# main.net
KiCad netlist of a schematic drawn in EAGLE
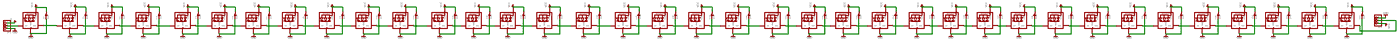
[diagram p0: schematic, sheet 1, overview]
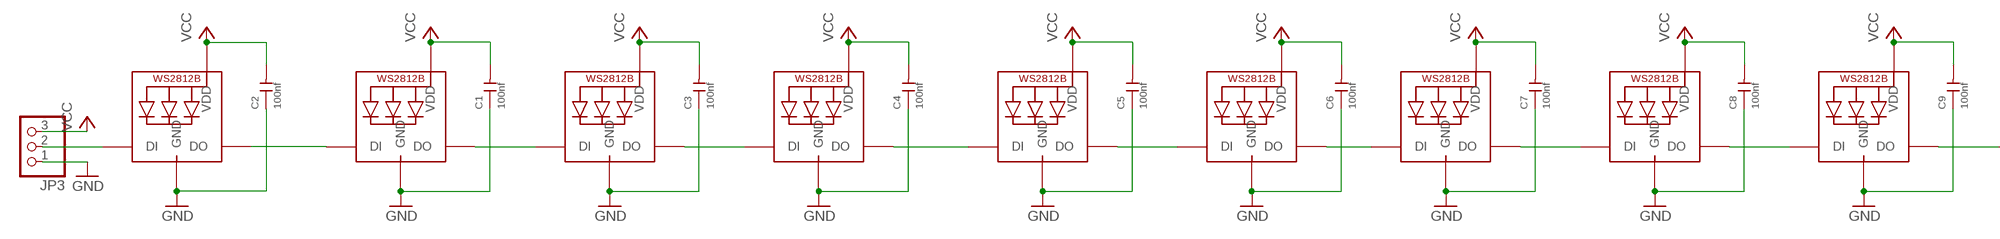
[diagram p1: schematic, sheet 1, part 1 of 4]
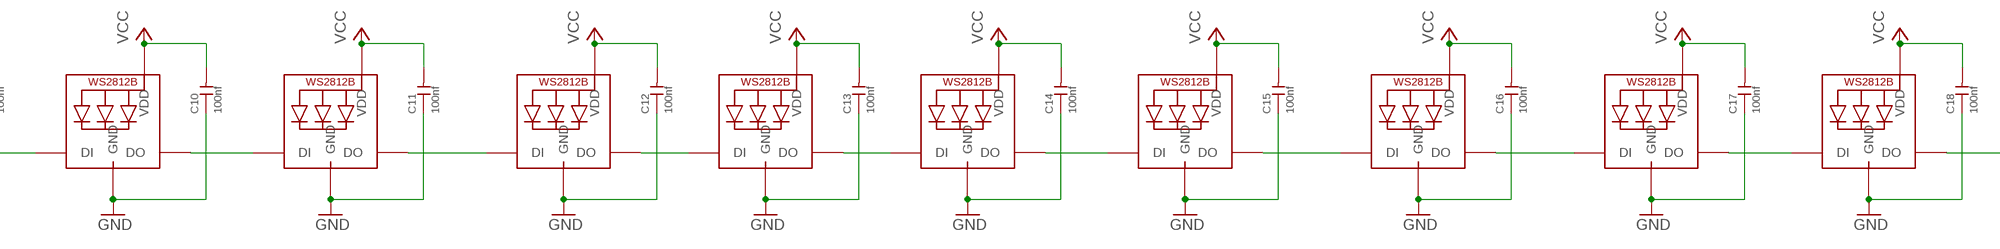
[diagram p2: schematic, sheet 1, part 2 of 4]
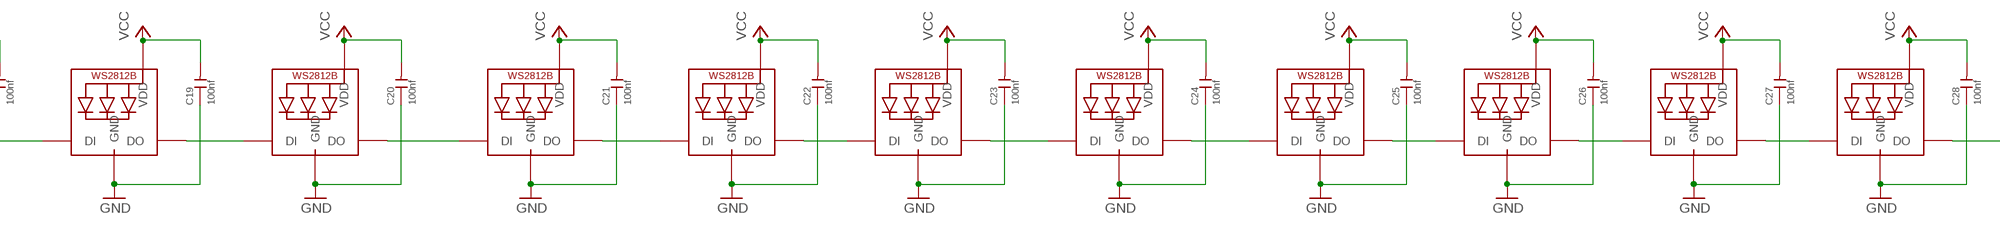
[diagram p3: schematic, sheet 1, part 3 of 4]
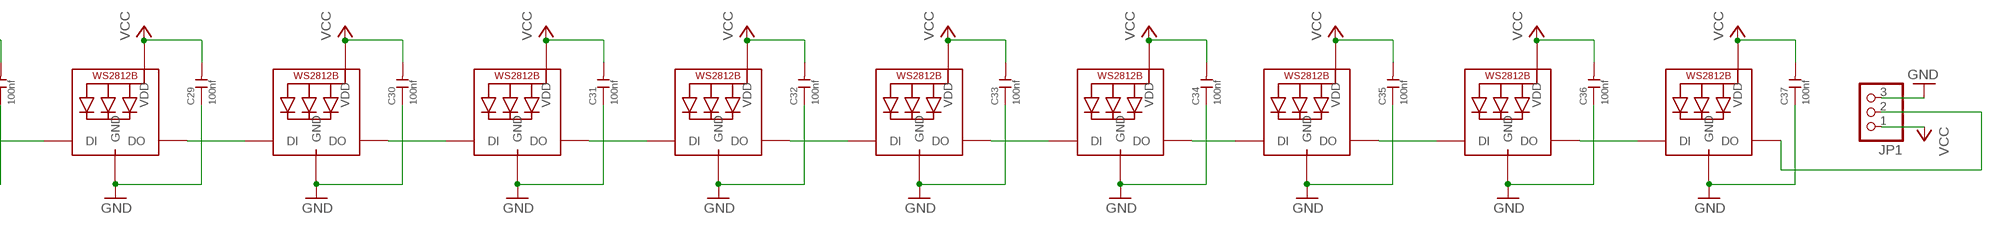
[diagram p4: schematic, sheet 1, part 4 of 4]

(export (version "E")
  (design (tool "Eeschema 10.0.6"))
  (components
    (comp (ref "C1")
      (value "100nf")
      (footprint "eagle-import:C0805")
      (fields (field (name "MPN") "CC0805KRX7R9BB104"))
      (libsource (lib "eagle-import") (part "CERAMIC-100NF-50V-10%-X7R(0805)"))
    )
    (comp (ref "C2")
      (value "100nf")
      (footprint "eagle-import:C0805")
      (fields (field (name "MPN") "CC0805KRX7R9BB104"))
      (libsource (lib "eagle-import") (part "CERAMIC-100NF-50V-10%-X7R(0805)"))
    )
    (comp (ref "C3")
      (value "100nf")
      (footprint "eagle-import:C0805")
      (fields (field (name "MPN") "CC0805KRX7R9BB104"))
      (libsource (lib "eagle-import") (part "CERAMIC-100NF-50V-10%-X7R(0805)"))
    )
    (comp (ref "C4")
      (value "100nf")
      (footprint "eagle-import:C0805")
      (fields (field (name "MPN") "CC0805KRX7R9BB104"))
      (libsource (lib "eagle-import") (part "CERAMIC-100NF-50V-10%-X7R(0805)"))
    )
    (comp (ref "C5")
      (value "100nf")
      (footprint "eagle-import:C0805")
      (fields (field (name "MPN") "CC0805KRX7R9BB104"))
      (libsource (lib "eagle-import") (part "CERAMIC-100NF-50V-10%-X7R(0805)"))
    )
    (comp (ref "C6")
      (value "100nf")
      (footprint "eagle-import:C0805")
      (fields (field (name "MPN") "CC0805KRX7R9BB104"))
      (libsource (lib "eagle-import") (part "CERAMIC-100NF-50V-10%-X7R(0805)"))
    )
    (comp (ref "C7")
      (value "100nf")
      (footprint "eagle-import:C0805")
      (fields (field (name "MPN") "CC0805KRX7R9BB104"))
      (libsource (lib "eagle-import") (part "CERAMIC-100NF-50V-10%-X7R(0805)"))
    )
    (comp (ref "C8")
      (value "100nf")
      (footprint "eagle-import:C0805")
      (fields (field (name "MPN") "CC0805KRX7R9BB104"))
      (libsource (lib "eagle-import") (part "CERAMIC-100NF-50V-10%-X7R(0805)"))
    )
    (comp (ref "C9")
      (value "100nf")
      (footprint "eagle-import:C0805")
      (fields (field (name "MPN") "CC0805KRX7R9BB104"))
      (libsource (lib "eagle-import") (part "CERAMIC-100NF-50V-10%-X7R(0805)"))
    )
    (comp (ref "C10")
      (value "100nf")
      (footprint "eagle-import:C0805")
      (fields (field (name "MPN") "CC0805KRX7R9BB104"))
      (libsource (lib "eagle-import") (part "CERAMIC-100NF-50V-10%-X7R(0805)"))
    )
    (comp (ref "C11")
      (value "100nf")
      (footprint "eagle-import:C0805")
      (fields (field (name "MPN") "CC0805KRX7R9BB104"))
      (libsource (lib "eagle-import") (part "CERAMIC-100NF-50V-10%-X7R(0805)"))
    )
    (comp (ref "C12")
      (value "100nf")
      (footprint "eagle-import:C0805")
      (fields (field (name "MPN") "CC0805KRX7R9BB104"))
      (libsource (lib "eagle-import") (part "CERAMIC-100NF-50V-10%-X7R(0805)"))
    )
    (comp (ref "C13")
      (value "100nf")
      (footprint "eagle-import:C0805")
      (fields (field (name "MPN") "CC0805KRX7R9BB104"))
      (libsource (lib "eagle-import") (part "CERAMIC-100NF-50V-10%-X7R(0805)"))
    )
    (comp (ref "C14")
      (value "100nf")
      (footprint "eagle-import:C0805")
      (fields (field (name "MPN") "CC0805KRX7R9BB104"))
      (libsource (lib "eagle-import") (part "CERAMIC-100NF-50V-10%-X7R(0805)"))
    )
    (comp (ref "C15")
      (value "100nf")
      (footprint "eagle-import:C0805")
      (fields (field (name "MPN") "CC0805KRX7R9BB104"))
      (libsource (lib "eagle-import") (part "CERAMIC-100NF-50V-10%-X7R(0805)"))
    )
    (comp (ref "C16")
      (value "100nf")
      (footprint "eagle-import:C0805")
      (fields (field (name "MPN") "CC0805KRX7R9BB104"))
      (libsource (lib "eagle-import") (part "CERAMIC-100NF-50V-10%-X7R(0805)"))
    )
    (comp (ref "C17")
      (value "100nf")
      (footprint "eagle-import:C0805")
      (fields (field (name "MPN") "CC0805KRX7R9BB104"))
      (libsource (lib "eagle-import") (part "CERAMIC-100NF-50V-10%-X7R(0805)"))
    )
    (comp (ref "C18")
      (value "100nf")
      (footprint "eagle-import:C0805")
      (fields (field (name "MPN") "CC0805KRX7R9BB104"))
      (libsource (lib "eagle-import") (part "CERAMIC-100NF-50V-10%-X7R(0805)"))
    )
    (comp (ref "C19")
      (value "100nf")
      (footprint "eagle-import:C0805")
      (fields (field (name "MPN") "CC0805KRX7R9BB104"))
      (libsource (lib "eagle-import") (part "CERAMIC-100NF-50V-10%-X7R(0805)"))
    )
    (comp (ref "C20")
      (value "100nf")
      (footprint "eagle-import:C0805")
      (fields (field (name "MPN") "CC0805KRX7R9BB104"))
      (libsource (lib "eagle-import") (part "CERAMIC-100NF-50V-10%-X7R(0805)"))
    )
    (comp (ref "C21")
      (value "100nf")
      (footprint "eagle-import:C0805")
      (fields (field (name "MPN") "CC0805KRX7R9BB104"))
      (libsource (lib "eagle-import") (part "CERAMIC-100NF-50V-10%-X7R(0805)"))
    )
    (comp (ref "C22")
      (value "100nf")
      (footprint "eagle-import:C0805")
      (fields (field (name "MPN") "CC0805KRX7R9BB104"))
      (libsource (lib "eagle-import") (part "CERAMIC-100NF-50V-10%-X7R(0805)"))
    )
    (comp (ref "C23")
      (value "100nf")
      (footprint "eagle-import:C0805")
      (fields (field (name "MPN") "CC0805KRX7R9BB104"))
      (libsource (lib "eagle-import") (part "CERAMIC-100NF-50V-10%-X7R(0805)"))
    )
    (comp (ref "C24")
      (value "100nf")
      (footprint "eagle-import:C0805")
      (fields (field (name "MPN") "CC0805KRX7R9BB104"))
      (libsource (lib "eagle-import") (part "CERAMIC-100NF-50V-10%-X7R(0805)"))
    )
    (comp (ref "C25")
      (value "100nf")
      (footprint "eagle-import:C0805")
      (fields (field (name "MPN") "CC0805KRX7R9BB104"))
      (libsource (lib "eagle-import") (part "CERAMIC-100NF-50V-10%-X7R(0805)"))
    )
    (comp (ref "C26")
      (value "100nf")
      (footprint "eagle-import:C0805")
      (fields (field (name "MPN") "CC0805KRX7R9BB104"))
      (libsource (lib "eagle-import") (part "CERAMIC-100NF-50V-10%-X7R(0805)"))
    )
    (comp (ref "C27")
      (value "100nf")
      (footprint "eagle-import:C0805")
      (fields (field (name "MPN") "CC0805KRX7R9BB104"))
      (libsource (lib "eagle-import") (part "CERAMIC-100NF-50V-10%-X7R(0805)"))
    )
    (comp (ref "C28")
      (value "100nf")
      (footprint "eagle-import:C0805")
      (fields (field (name "MPN") "CC0805KRX7R9BB104"))
      (libsource (lib "eagle-import") (part "CERAMIC-100NF-50V-10%-X7R(0805)"))
    )
    (comp (ref "C29")
      (value "100nf")
      (footprint "eagle-import:C0805")
      (fields (field (name "MPN") "CC0805KRX7R9BB104"))
      (libsource (lib "eagle-import") (part "CERAMIC-100NF-50V-10%-X7R(0805)"))
    )
    (comp (ref "C30")
      (value "100nf")
      (footprint "eagle-import:C0805")
      (fields (field (name "MPN") "CC0805KRX7R9BB104"))
      (libsource (lib "eagle-import") (part "CERAMIC-100NF-50V-10%-X7R(0805)"))
    )
    (comp (ref "C31")
      (value "100nf")
      (footprint "eagle-import:C0805")
      (fields (field (name "MPN") "CC0805KRX7R9BB104"))
      (libsource (lib "eagle-import") (part "CERAMIC-100NF-50V-10%-X7R(0805)"))
    )
    (comp (ref "C32")
      (value "100nf")
      (footprint "eagle-import:C0805")
      (fields (field (name "MPN") "CC0805KRX7R9BB104"))
      (libsource (lib "eagle-import") (part "CERAMIC-100NF-50V-10%-X7R(0805)"))
    )
    (comp (ref "C33")
      (value "100nf")
      (footprint "eagle-import:C0805")
      (fields (field (name "MPN") "CC0805KRX7R9BB104"))
      (libsource (lib "eagle-import") (part "CERAMIC-100NF-50V-10%-X7R(0805)"))
    )
    (comp (ref "C34")
      (value "100nf")
      (footprint "eagle-import:C0805")
      (fields (field (name "MPN") "CC0805KRX7R9BB104"))
      (libsource (lib "eagle-import") (part "CERAMIC-100NF-50V-10%-X7R(0805)"))
    )
    (comp (ref "C35")
      (value "100nf")
      (footprint "eagle-import:C0805")
      (fields (field (name "MPN") "CC0805KRX7R9BB104"))
      (libsource (lib "eagle-import") (part "CERAMIC-100NF-50V-10%-X7R(0805)"))
    )
    (comp (ref "C36")
      (value "100nf")
      (footprint "eagle-import:C0805")
      (fields (field (name "MPN") "CC0805KRX7R9BB104"))
      (libsource (lib "eagle-import") (part "CERAMIC-100NF-50V-10%-X7R(0805)"))
    )
    (comp (ref "C37")
      (value "100nf")
      (footprint "eagle-import:C0805")
      (fields (field (name "MPN") "CC0805KRX7R9BB104"))
      (libsource (lib "eagle-import") (part "CERAMIC-100NF-50V-10%-X7R(0805)"))
    )
    (comp (ref "JP1")
      (value "PINHD-1X3")
      (footprint "eagle-import:1X03")
      (libsource (lib "eagle-import") (part "PINHD-1X3"))
    )
    (comp (ref "JP3")
      (value "PINHD-1X3")
      (footprint "eagle-import:1X03")
      (libsource (lib "eagle-import") (part "PINHD-1X3"))
    )
    (comp (ref "L")
      (value "WS2812B5050")
      (footprint "eagle-import:WS2812B")
      (libsource (lib "eagle-import") (part "WS2812B5050"))
    )
    (comp (ref "LED1")
      (value "WS2812B5050")
      (footprint "eagle-import:WS2812B")
      (libsource (lib "eagle-import") (part "WS2812B5050"))
    )
    (comp (ref "LED3")
      (value "WS2812B5050")
      (footprint "eagle-import:WS2812B")
      (libsource (lib "eagle-import") (part "WS2812B5050"))
    )
    (comp (ref "LED4")
      (value "WS2812B5050")
      (footprint "eagle-import:WS2812B")
      (libsource (lib "eagle-import") (part "WS2812B5050"))
    )
    (comp (ref "LED5")
      (value "WS2812B5050")
      (footprint "eagle-import:WS2812B")
      (libsource (lib "eagle-import") (part "WS2812B5050"))
    )
    (comp (ref "LED6")
      (value "WS2812B5050")
      (footprint "eagle-import:WS2812B")
      (libsource (lib "eagle-import") (part "WS2812B5050"))
    )
    (comp (ref "LED7")
      (value "WS2812B5050")
      (footprint "eagle-import:WS2812B")
      (libsource (lib "eagle-import") (part "WS2812B5050"))
    )
    (comp (ref "LED8")
      (value "WS2812B5050")
      (footprint "eagle-import:WS2812B")
      (libsource (lib "eagle-import") (part "WS2812B5050"))
    )
    (comp (ref "LED9")
      (value "WS2812B5050")
      (footprint "eagle-import:WS2812B")
      (libsource (lib "eagle-import") (part "WS2812B5050"))
    )
    (comp (ref "LED10")
      (value "WS2812B5050")
      (footprint "eagle-import:WS2812B")
      (libsource (lib "eagle-import") (part "WS2812B5050"))
    )
    (comp (ref "LED11")
      (value "WS2812B5050")
      (footprint "eagle-import:WS2812B")
      (libsource (lib "eagle-import") (part "WS2812B5050"))
    )
    (comp (ref "LED12")
      (value "WS2812B5050")
      (footprint "eagle-import:WS2812B")
      (libsource (lib "eagle-import") (part "WS2812B5050"))
    )
    (comp (ref "LED13")
      (value "WS2812B5050")
      (footprint "eagle-import:WS2812B")
      (libsource (lib "eagle-import") (part "WS2812B5050"))
    )
    (comp (ref "LED14")
      (value "WS2812B5050")
      (footprint "eagle-import:WS2812B")
      (libsource (lib "eagle-import") (part "WS2812B5050"))
    )
    (comp (ref "LED15")
      (value "WS2812B5050")
      (footprint "eagle-import:WS2812B")
      (libsource (lib "eagle-import") (part "WS2812B5050"))
    )
    (comp (ref "LED16")
      (value "WS2812B5050")
      (footprint "eagle-import:WS2812B")
      (libsource (lib "eagle-import") (part "WS2812B5050"))
    )
    (comp (ref "LED17")
      (value "WS2812B5050")
      (footprint "eagle-import:WS2812B")
      (libsource (lib "eagle-import") (part "WS2812B5050"))
    )
    (comp (ref "LED18")
      (value "WS2812B5050")
      (footprint "eagle-import:WS2812B")
      (libsource (lib "eagle-import") (part "WS2812B5050"))
    )
    (comp (ref "LED19")
      (value "WS2812B5050")
      (footprint "eagle-import:WS2812B")
      (libsource (lib "eagle-import") (part "WS2812B5050"))
    )
    (comp (ref "LED20")
      (value "WS2812B5050")
      (footprint "eagle-import:WS2812B")
      (libsource (lib "eagle-import") (part "WS2812B5050"))
    )
    (comp (ref "LED21")
      (value "WS2812B5050")
      (footprint "eagle-import:WS2812B")
      (libsource (lib "eagle-import") (part "WS2812B5050"))
    )
    (comp (ref "LED22")
      (value "WS2812B5050")
      (footprint "eagle-import:WS2812B")
      (libsource (lib "eagle-import") (part "WS2812B5050"))
    )
    (comp (ref "LED23")
      (value "WS2812B5050")
      (footprint "eagle-import:WS2812B")
      (libsource (lib "eagle-import") (part "WS2812B5050"))
    )
    (comp (ref "LED24")
      (value "WS2812B5050")
      (footprint "eagle-import:WS2812B")
      (libsource (lib "eagle-import") (part "WS2812B5050"))
    )
    (comp (ref "LED25")
      (value "WS2812B5050")
      (footprint "eagle-import:WS2812B")
      (libsource (lib "eagle-import") (part "WS2812B5050"))
    )
    (comp (ref "LED26")
      (value "WS2812B5050")
      (footprint "eagle-import:WS2812B")
      (libsource (lib "eagle-import") (part "WS2812B5050"))
    )
    (comp (ref "LED27")
      (value "WS2812B5050")
      (footprint "eagle-import:WS2812B")
      (libsource (lib "eagle-import") (part "WS2812B5050"))
    )
    (comp (ref "LED28")
      (value "WS2812B5050")
      (footprint "eagle-import:WS2812B")
      (libsource (lib "eagle-import") (part "WS2812B5050"))
    )
    (comp (ref "LED29")
      (value "WS2812B5050")
      (footprint "eagle-import:WS2812B")
      (libsource (lib "eagle-import") (part "WS2812B5050"))
    )
    (comp (ref "LED30")
      (value "WS2812B5050")
      (footprint "eagle-import:WS2812B")
      (libsource (lib "eagle-import") (part "WS2812B5050"))
    )
    (comp (ref "LED31")
      (value "WS2812B5050")
      (footprint "eagle-import:WS2812B")
      (libsource (lib "eagle-import") (part "WS2812B5050"))
    )
    (comp (ref "LED32")
      (value "WS2812B5050")
      (footprint "eagle-import:WS2812B")
      (libsource (lib "eagle-import") (part "WS2812B5050"))
    )
    (comp (ref "LED33")
      (value "WS2812B5050")
      (footprint "eagle-import:WS2812B")
      (libsource (lib "eagle-import") (part "WS2812B5050"))
    )
    (comp (ref "LED34")
      (value "WS2812B5050")
      (footprint "eagle-import:WS2812B")
      (libsource (lib "eagle-import") (part "WS2812B5050"))
    )
    (comp (ref "LED35")
      (value "WS2812B5050")
      (footprint "eagle-import:WS2812B")
      (libsource (lib "eagle-import") (part "WS2812B5050"))
    )
    (comp (ref "LED36")
      (value "WS2812B5050")
      (footprint "eagle-import:WS2812B")
      (libsource (lib "eagle-import") (part "WS2812B5050"))
    )
    (comp (ref "LED37")
      (value "WS2812B5050")
      (footprint "eagle-import:WS2812B")
      (libsource (lib "eagle-import") (part "WS2812B5050"))
    )
  )
  (nets
    (net (code "1") (name "GND") (class "Default")
      (node (ref "C1") (pin "1") (pinfunction "1_1") (pintype "passive"))
      (node (ref "C10") (pin "1") (pinfunction "1_1") (pintype "passive"))
      (node (ref "C11") (pin "1") (pinfunction "1_1") (pintype "passive"))
      (node (ref "C12") (pin "1") (pinfunction "1_1") (pintype "passive"))
      (node (ref "C13") (pin "1") (pinfunction "1_1") (pintype "passive"))
      (node (ref "C14") (pin "1") (pinfunction "1_1") (pintype "passive"))
      (node (ref "C15") (pin "1") (pinfunction "1_1") (pintype "passive"))
      (node (ref "C16") (pin "1") (pinfunction "1_1") (pintype "passive"))
      (node (ref "C17") (pin "1") (pinfunction "1_1") (pintype "passive"))
      (node (ref "C18") (pin "1") (pinfunction "1_1") (pintype "passive"))
      (node (ref "C19") (pin "1") (pinfunction "1_1") (pintype "passive"))
      (node (ref "C2") (pin "1") (pinfunction "1_1") (pintype "passive"))
      (node (ref "C20") (pin "1") (pinfunction "1_1") (pintype "passive"))
      (node (ref "C21") (pin "1") (pinfunction "1_1") (pintype "passive"))
      (node (ref "C22") (pin "1") (pinfunction "1_1") (pintype "passive"))
      (node (ref "C23") (pin "1") (pinfunction "1_1") (pintype "passive"))
      (node (ref "C24") (pin "1") (pinfunction "1_1") (pintype "passive"))
      (node (ref "C25") (pin "1") (pinfunction "1_1") (pintype "passive"))
      (node (ref "C26") (pin "1") (pinfunction "1_1") (pintype "passive"))
      (node (ref "C27") (pin "1") (pinfunction "1_1") (pintype "passive"))
      (node (ref "C28") (pin "1") (pinfunction "1_1") (pintype "passive"))
      (node (ref "C29") (pin "1") (pinfunction "1_1") (pintype "passive"))
      (node (ref "C3") (pin "1") (pinfunction "1_1") (pintype "passive"))
      (node (ref "C30") (pin "1") (pinfunction "1_1") (pintype "passive"))
      (node (ref "C31") (pin "1") (pinfunction "1_1") (pintype "passive"))
      (node (ref "C32") (pin "1") (pinfunction "1_1") (pintype "passive"))
      (node (ref "C33") (pin "1") (pinfunction "1_1") (pintype "passive"))
      (node (ref "C34") (pin "1") (pinfunction "1_1") (pintype "passive"))
      (node (ref "C35") (pin "1") (pinfunction "1_1") (pintype "passive"))
      (node (ref "C36") (pin "1") (pinfunction "1_1") (pintype "passive"))
      (node (ref "C37") (pin "1") (pinfunction "1_1") (pintype "passive"))
      (node (ref "C4") (pin "1") (pinfunction "1_1") (pintype "passive"))
      (node (ref "C5") (pin "1") (pinfunction "1_1") (pintype "passive"))
      (node (ref "C6") (pin "1") (pinfunction "1_1") (pintype "passive"))
      (node (ref "C7") (pin "1") (pinfunction "1_1") (pintype "passive"))
      (node (ref "C8") (pin "1") (pinfunction "1_1") (pintype "passive"))
      (node (ref "C9") (pin "1") (pinfunction "1_1") (pintype "passive"))
      (node (ref "JP1") (pin "3") (pinfunction "3_3") (pintype "passive"))
      (node (ref "JP3") (pin "1") (pinfunction "1_1") (pintype "passive"))
      (node (ref "L") (pin "3-GND") (pinfunction "GND_3-GND") (pintype "power_in"))
      (node (ref "LED1") (pin "3-GND") (pinfunction "GND_3-GND") (pintype "power_in"))
      (node (ref "LED10") (pin "3-GND") (pinfunction "GND_3-GND") (pintype "power_in"))
      (node (ref "LED11") (pin "3-GND") (pinfunction "GND_3-GND") (pintype "power_in"))
      (node (ref "LED12") (pin "3-GND") (pinfunction "GND_3-GND") (pintype "power_in"))
      (node (ref "LED13") (pin "3-GND") (pinfunction "GND_3-GND") (pintype "power_in"))
      (node (ref "LED14") (pin "3-GND") (pinfunction "GND_3-GND") (pintype "power_in"))
      (node (ref "LED15") (pin "3-GND") (pinfunction "GND_3-GND") (pintype "power_in"))
      (node (ref "LED16") (pin "3-GND") (pinfunction "GND_3-GND") (pintype "power_in"))
      (node (ref "LED17") (pin "3-GND") (pinfunction "GND_3-GND") (pintype "power_in"))
      (node (ref "LED18") (pin "3-GND") (pinfunction "GND_3-GND") (pintype "power_in"))
      (node (ref "LED19") (pin "3-GND") (pinfunction "GND_3-GND") (pintype "power_in"))
      (node (ref "LED20") (pin "3-GND") (pinfunction "GND_3-GND") (pintype "power_in"))
      (node (ref "LED21") (pin "3-GND") (pinfunction "GND_3-GND") (pintype "power_in"))
      (node (ref "LED22") (pin "3-GND") (pinfunction "GND_3-GND") (pintype "power_in"))
      (node (ref "LED23") (pin "3-GND") (pinfunction "GND_3-GND") (pintype "power_in"))
      (node (ref "LED24") (pin "3-GND") (pinfunction "GND_3-GND") (pintype "power_in"))
      (node (ref "LED25") (pin "3-GND") (pinfunction "GND_3-GND") (pintype "power_in"))
      (node (ref "LED26") (pin "3-GND") (pinfunction "GND_3-GND") (pintype "power_in"))
      (node (ref "LED27") (pin "3-GND") (pinfunction "GND_3-GND") (pintype "power_in"))
      (node (ref "LED28") (pin "3-GND") (pinfunction "GND_3-GND") (pintype "power_in"))
      (node (ref "LED29") (pin "3-GND") (pinfunction "GND_3-GND") (pintype "power_in"))
      (node (ref "LED3") (pin "3-GND") (pinfunction "GND_3-GND") (pintype "power_in"))
      (node (ref "LED30") (pin "3-GND") (pinfunction "GND_3-GND") (pintype "power_in"))
      (node (ref "LED31") (pin "3-GND") (pinfunction "GND_3-GND") (pintype "power_in"))
      (node (ref "LED32") (pin "3-GND") (pinfunction "GND_3-GND") (pintype "power_in"))
      (node (ref "LED33") (pin "3-GND") (pinfunction "GND_3-GND") (pintype "power_in"))
      (node (ref "LED34") (pin "3-GND") (pinfunction "GND_3-GND") (pintype "power_in"))
      (node (ref "LED35") (pin "3-GND") (pinfunction "GND_3-GND") (pintype "power_in"))
      (node (ref "LED36") (pin "3-GND") (pinfunction "GND_3-GND") (pintype "power_in"))
      (node (ref "LED37") (pin "3-GND") (pinfunction "GND_3-GND") (pintype "power_in"))
      (node (ref "LED4") (pin "3-GND") (pinfunction "GND_3-GND") (pintype "power_in"))
      (node (ref "LED5") (pin "3-GND") (pinfunction "GND_3-GND") (pintype "power_in"))
      (node (ref "LED6") (pin "3-GND") (pinfunction "GND_3-GND") (pintype "power_in"))
      (node (ref "LED7") (pin "3-GND") (pinfunction "GND_3-GND") (pintype "power_in"))
      (node (ref "LED8") (pin "3-GND") (pinfunction "GND_3-GND") (pintype "power_in"))
      (node (ref "LED9") (pin "3-GND") (pinfunction "GND_3-GND") (pintype "power_in"))
    )
    (net (code "2") (name "Net-(L-DI)") (class "Default")
      (node (ref "JP3") (pin "2") (pinfunction "2_2") (pintype "passive"))
      (node (ref "L") (pin "4-DIN") (pinfunction "DI_4-DIN") (pintype "input"))
    )
    (net (code "3") (name "Net-(L-DO)") (class "Default")
      (node (ref "L") (pin "2-DOUT") (pinfunction "DO_2-DOUT") (pintype "output"))
      (node (ref "LED1") (pin "4-DIN") (pinfunction "DI_4-DIN") (pintype "input"))
    )
    (net (code "4") (name "Net-(LED1-DO)") (class "Default")
      (node (ref "LED1") (pin "2-DOUT") (pinfunction "DO_2-DOUT") (pintype "output"))
      (node (ref "LED3") (pin "4-DIN") (pinfunction "DI_4-DIN") (pintype "input"))
    )
    (net (code "5") (name "Net-(LED3-DO)") (class "Default")
      (node (ref "LED3") (pin "2-DOUT") (pinfunction "DO_2-DOUT") (pintype "output"))
      (node (ref "LED4") (pin "4-DIN") (pinfunction "DI_4-DIN") (pintype "input"))
    )
    (net (code "6") (name "Net-(LED4-DO)") (class "Default")
      (node (ref "LED4") (pin "2-DOUT") (pinfunction "DO_2-DOUT") (pintype "output"))
      (node (ref "LED5") (pin "4-DIN") (pinfunction "DI_4-DIN") (pintype "input"))
    )
    (net (code "7") (name "Net-(LED5-DO)") (class "Default")
      (node (ref "LED5") (pin "2-DOUT") (pinfunction "DO_2-DOUT") (pintype "output"))
      (node (ref "LED6") (pin "4-DIN") (pinfunction "DI_4-DIN") (pintype "input"))
    )
    (net (code "8") (name "Net-(LED6-DO)") (class "Default")
      (node (ref "LED6") (pin "2-DOUT") (pinfunction "DO_2-DOUT") (pintype "output"))
      (node (ref "LED7") (pin "4-DIN") (pinfunction "DI_4-DIN") (pintype "input"))
    )
    (net (code "9") (name "Net-(LED7-DO)") (class "Default")
      (node (ref "LED7") (pin "2-DOUT") (pinfunction "DO_2-DOUT") (pintype "output"))
      (node (ref "LED8") (pin "4-DIN") (pinfunction "DI_4-DIN") (pintype "input"))
    )
    (net (code "10") (name "Net-(LED8-DO)") (class "Default")
      (node (ref "LED8") (pin "2-DOUT") (pinfunction "DO_2-DOUT") (pintype "output"))
      (node (ref "LED9") (pin "4-DIN") (pinfunction "DI_4-DIN") (pintype "input"))
    )
    (net (code "11") (name "Net-(LED10-DI)") (class "Default")
      (node (ref "LED10") (pin "4-DIN") (pinfunction "DI_4-DIN") (pintype "input"))
      (node (ref "LED9") (pin "2-DOUT") (pinfunction "DO_2-DOUT") (pintype "output"))
    )
    (net (code "12") (name "Net-(LED10-DO)") (class "Default")
      (node (ref "LED10") (pin "2-DOUT") (pinfunction "DO_2-DOUT") (pintype "output"))
      (node (ref "LED11") (pin "4-DIN") (pinfunction "DI_4-DIN") (pintype "input"))
    )
    (net (code "13") (name "Net-(LED11-DO)") (class "Default")
      (node (ref "LED11") (pin "2-DOUT") (pinfunction "DO_2-DOUT") (pintype "output"))
      (node (ref "LED12") (pin "4-DIN") (pinfunction "DI_4-DIN") (pintype "input"))
    )
    (net (code "14") (name "Net-(LED12-DO)") (class "Default")
      (node (ref "LED12") (pin "2-DOUT") (pinfunction "DO_2-DOUT") (pintype "output"))
      (node (ref "LED13") (pin "4-DIN") (pinfunction "DI_4-DIN") (pintype "input"))
    )
    (net (code "15") (name "Net-(LED13-DO)") (class "Default")
      (node (ref "LED13") (pin "2-DOUT") (pinfunction "DO_2-DOUT") (pintype "output"))
      (node (ref "LED14") (pin "4-DIN") (pinfunction "DI_4-DIN") (pintype "input"))
    )
    (net (code "16") (name "Net-(LED14-DO)") (class "Default")
      (node (ref "LED14") (pin "2-DOUT") (pinfunction "DO_2-DOUT") (pintype "output"))
      (node (ref "LED15") (pin "4-DIN") (pinfunction "DI_4-DIN") (pintype "input"))
    )
    (net (code "17") (name "Net-(LED15-DO)") (class "Default")
      (node (ref "LED15") (pin "2-DOUT") (pinfunction "DO_2-DOUT") (pintype "output"))
      (node (ref "LED16") (pin "4-DIN") (pinfunction "DI_4-DIN") (pintype "input"))
    )
    (net (code "18") (name "Net-(LED16-DO)") (class "Default")
      (node (ref "LED16") (pin "2-DOUT") (pinfunction "DO_2-DOUT") (pintype "output"))
      (node (ref "LED17") (pin "4-DIN") (pinfunction "DI_4-DIN") (pintype "input"))
    )
    (net (code "19") (name "Net-(LED17-DO)") (class "Default")
      (node (ref "LED17") (pin "2-DOUT") (pinfunction "DO_2-DOUT") (pintype "output"))
      (node (ref "LED18") (pin "4-DIN") (pinfunction "DI_4-DIN") (pintype "input"))
    )
    (net (code "20") (name "Net-(LED18-DO)") (class "Default")
      (node (ref "LED18") (pin "2-DOUT") (pinfunction "DO_2-DOUT") (pintype "output"))
      (node (ref "LED19") (pin "4-DIN") (pinfunction "DI_4-DIN") (pintype "input"))
    )
    (net (code "21") (name "Net-(LED19-DO)") (class "Default")
      (node (ref "LED19") (pin "2-DOUT") (pinfunction "DO_2-DOUT") (pintype "output"))
      (node (ref "LED20") (pin "4-DIN") (pinfunction "DI_4-DIN") (pintype "input"))
    )
    (net (code "22") (name "Net-(LED20-DO)") (class "Default")
      (node (ref "LED20") (pin "2-DOUT") (pinfunction "DO_2-DOUT") (pintype "output"))
      (node (ref "LED21") (pin "4-DIN") (pinfunction "DI_4-DIN") (pintype "input"))
    )
    (net (code "23") (name "Net-(LED21-DO)") (class "Default")
      (node (ref "LED21") (pin "2-DOUT") (pinfunction "DO_2-DOUT") (pintype "output"))
      (node (ref "LED22") (pin "4-DIN") (pinfunction "DI_4-DIN") (pintype "input"))
    )
    (net (code "24") (name "Net-(LED22-DO)") (class "Default")
      (node (ref "LED22") (pin "2-DOUT") (pinfunction "DO_2-DOUT") (pintype "output"))
      (node (ref "LED23") (pin "4-DIN") (pinfunction "DI_4-DIN") (pintype "input"))
    )
    (net (code "25") (name "Net-(LED23-DO)") (class "Default")
      (node (ref "LED23") (pin "2-DOUT") (pinfunction "DO_2-DOUT") (pintype "output"))
      (node (ref "LED24") (pin "4-DIN") (pinfunction "DI_4-DIN") (pintype "input"))
    )
    (net (code "26") (name "Net-(LED24-DO)") (class "Default")
      (node (ref "LED24") (pin "2-DOUT") (pinfunction "DO_2-DOUT") (pintype "output"))
      (node (ref "LED25") (pin "4-DIN") (pinfunction "DI_4-DIN") (pintype "input"))
    )
    (net (code "27") (name "Net-(LED25-DO)") (class "Default")
      (node (ref "LED25") (pin "2-DOUT") (pinfunction "DO_2-DOUT") (pintype "output"))
      (node (ref "LED26") (pin "4-DIN") (pinfunction "DI_4-DIN") (pintype "input"))
    )
    (net (code "28") (name "Net-(LED26-DO)") (class "Default")
      (node (ref "LED26") (pin "2-DOUT") (pinfunction "DO_2-DOUT") (pintype "output"))
      (node (ref "LED27") (pin "4-DIN") (pinfunction "DI_4-DIN") (pintype "input"))
    )
    (net (code "29") (name "Net-(LED27-DO)") (class "Default")
      (node (ref "LED27") (pin "2-DOUT") (pinfunction "DO_2-DOUT") (pintype "output"))
      (node (ref "LED28") (pin "4-DIN") (pinfunction "DI_4-DIN") (pintype "input"))
    )
    (net (code "30") (name "Net-(LED28-DO)") (class "Default")
      (node (ref "LED28") (pin "2-DOUT") (pinfunction "DO_2-DOUT") (pintype "output"))
      (node (ref "LED29") (pin "4-DIN") (pinfunction "DI_4-DIN") (pintype "input"))
    )
    (net (code "31") (name "Net-(LED29-DO)") (class "Default")
      (node (ref "LED29") (pin "2-DOUT") (pinfunction "DO_2-DOUT") (pintype "output"))
      (node (ref "LED30") (pin "4-DIN") (pinfunction "DI_4-DIN") (pintype "input"))
    )
    (net (code "32") (name "Net-(LED30-DO)") (class "Default")
      (node (ref "LED30") (pin "2-DOUT") (pinfunction "DO_2-DOUT") (pintype "output"))
      (node (ref "LED31") (pin "4-DIN") (pinfunction "DI_4-DIN") (pintype "input"))
    )
    (net (code "33") (name "Net-(LED31-DO)") (class "Default")
      (node (ref "LED31") (pin "2-DOUT") (pinfunction "DO_2-DOUT") (pintype "output"))
      (node (ref "LED32") (pin "4-DIN") (pinfunction "DI_4-DIN") (pintype "input"))
    )
    (net (code "34") (name "Net-(LED32-DO)") (class "Default")
      (node (ref "LED32") (pin "2-DOUT") (pinfunction "DO_2-DOUT") (pintype "output"))
      (node (ref "LED33") (pin "4-DIN") (pinfunction "DI_4-DIN") (pintype "input"))
    )
    (net (code "35") (name "Net-(LED33-DO)") (class "Default")
      (node (ref "LED33") (pin "2-DOUT") (pinfunction "DO_2-DOUT") (pintype "output"))
      (node (ref "LED34") (pin "4-DIN") (pinfunction "DI_4-DIN") (pintype "input"))
    )
    (net (code "36") (name "Net-(LED34-DO)") (class "Default")
      (node (ref "LED34") (pin "2-DOUT") (pinfunction "DO_2-DOUT") (pintype "output"))
      (node (ref "LED35") (pin "4-DIN") (pinfunction "DI_4-DIN") (pintype "input"))
    )
    (net (code "37") (name "Net-(LED35-DO)") (class "Default")
      (node (ref "LED35") (pin "2-DOUT") (pinfunction "DO_2-DOUT") (pintype "output"))
      (node (ref "LED36") (pin "4-DIN") (pinfunction "DI_4-DIN") (pintype "input"))
    )
    (net (code "38") (name "Net-(LED36-DO)") (class "Default")
      (node (ref "LED36") (pin "2-DOUT") (pinfunction "DO_2-DOUT") (pintype "output"))
      (node (ref "LED37") (pin "4-DIN") (pinfunction "DI_4-DIN") (pintype "input"))
    )
    (net (code "39") (name "Net-(LED37-DO)") (class "Default")
      (node (ref "JP1") (pin "2") (pinfunction "2_2") (pintype "passive"))
      (node (ref "LED37") (pin "2-DOUT") (pinfunction "DO_2-DOUT") (pintype "output"))
    )
    (net (code "40") (name "VCC") (class "Default")
      (node (ref "C1") (pin "2") (pinfunction "2_2") (pintype "passive"))
      (node (ref "C10") (pin "2") (pinfunction "2_2") (pintype "passive"))
      (node (ref "C11") (pin "2") (pinfunction "2_2") (pintype "passive"))
      (node (ref "C12") (pin "2") (pinfunction "2_2") (pintype "passive"))
      (node (ref "C13") (pin "2") (pinfunction "2_2") (pintype "passive"))
      (node (ref "C14") (pin "2") (pinfunction "2_2") (pintype "passive"))
      (node (ref "C15") (pin "2") (pinfunction "2_2") (pintype "passive"))
      (node (ref "C16") (pin "2") (pinfunction "2_2") (pintype "passive"))
      (node (ref "C17") (pin "2") (pinfunction "2_2") (pintype "passive"))
      (node (ref "C18") (pin "2") (pinfunction "2_2") (pintype "passive"))
      (node (ref "C19") (pin "2") (pinfunction "2_2") (pintype "passive"))
      (node (ref "C2") (pin "2") (pinfunction "2_2") (pintype "passive"))
      (node (ref "C20") (pin "2") (pinfunction "2_2") (pintype "passive"))
      (node (ref "C21") (pin "2") (pinfunction "2_2") (pintype "passive"))
      (node (ref "C22") (pin "2") (pinfunction "2_2") (pintype "passive"))
      (node (ref "C23") (pin "2") (pinfunction "2_2") (pintype "passive"))
      (node (ref "C24") (pin "2") (pinfunction "2_2") (pintype "passive"))
      (node (ref "C25") (pin "2") (pinfunction "2_2") (pintype "passive"))
      (node (ref "C26") (pin "2") (pinfunction "2_2") (pintype "passive"))
      (node (ref "C27") (pin "2") (pinfunction "2_2") (pintype "passive"))
      (node (ref "C28") (pin "2") (pinfunction "2_2") (pintype "passive"))
      (node (ref "C29") (pin "2") (pinfunction "2_2") (pintype "passive"))
      (node (ref "C3") (pin "2") (pinfunction "2_2") (pintype "passive"))
      (node (ref "C30") (pin "2") (pinfunction "2_2") (pintype "passive"))
      (node (ref "C31") (pin "2") (pinfunction "2_2") (pintype "passive"))
      (node (ref "C32") (pin "2") (pinfunction "2_2") (pintype "passive"))
      (node (ref "C33") (pin "2") (pinfunction "2_2") (pintype "passive"))
      (node (ref "C34") (pin "2") (pinfunction "2_2") (pintype "passive"))
      (node (ref "C35") (pin "2") (pinfunction "2_2") (pintype "passive"))
      (node (ref "C36") (pin "2") (pinfunction "2_2") (pintype "passive"))
      (node (ref "C37") (pin "2") (pinfunction "2_2") (pintype "passive"))
      (node (ref "C4") (pin "2") (pinfunction "2_2") (pintype "passive"))
      (node (ref "C5") (pin "2") (pinfunction "2_2") (pintype "passive"))
      (node (ref "C6") (pin "2") (pinfunction "2_2") (pintype "passive"))
      (node (ref "C7") (pin "2") (pinfunction "2_2") (pintype "passive"))
      (node (ref "C8") (pin "2") (pinfunction "2_2") (pintype "passive"))
      (node (ref "C9") (pin "2") (pinfunction "2_2") (pintype "passive"))
      (node (ref "JP1") (pin "1") (pinfunction "1_1") (pintype "passive"))
      (node (ref "JP3") (pin "3") (pinfunction "3_3") (pintype "passive"))
      (node (ref "L") (pin "1-VDD") (pinfunction "VDD_1-VDD") (pintype "power_in"))
      (node (ref "LED1") (pin "1-VDD") (pinfunction "VDD_1-VDD") (pintype "power_in"))
      (node (ref "LED10") (pin "1-VDD") (pinfunction "VDD_1-VDD") (pintype "power_in"))
      (node (ref "LED11") (pin "1-VDD") (pinfunction "VDD_1-VDD") (pintype "power_in"))
      (node (ref "LED12") (pin "1-VDD") (pinfunction "VDD_1-VDD") (pintype "power_in"))
      (node (ref "LED13") (pin "1-VDD") (pinfunction "VDD_1-VDD") (pintype "power_in"))
      (node (ref "LED14") (pin "1-VDD") (pinfunction "VDD_1-VDD") (pintype "power_in"))
      (node (ref "LED15") (pin "1-VDD") (pinfunction "VDD_1-VDD") (pintype "power_in"))
      (node (ref "LED16") (pin "1-VDD") (pinfunction "VDD_1-VDD") (pintype "power_in"))
      (node (ref "LED17") (pin "1-VDD") (pinfunction "VDD_1-VDD") (pintype "power_in"))
      (node (ref "LED18") (pin "1-VDD") (pinfunction "VDD_1-VDD") (pintype "power_in"))
      (node (ref "LED19") (pin "1-VDD") (pinfunction "VDD_1-VDD") (pintype "power_in"))
      (node (ref "LED20") (pin "1-VDD") (pinfunction "VDD_1-VDD") (pintype "power_in"))
      (node (ref "LED21") (pin "1-VDD") (pinfunction "VDD_1-VDD") (pintype "power_in"))
      (node (ref "LED22") (pin "1-VDD") (pinfunction "VDD_1-VDD") (pintype "power_in"))
      (node (ref "LED23") (pin "1-VDD") (pinfunction "VDD_1-VDD") (pintype "power_in"))
      (node (ref "LED24") (pin "1-VDD") (pinfunction "VDD_1-VDD") (pintype "power_in"))
      (node (ref "LED25") (pin "1-VDD") (pinfunction "VDD_1-VDD") (pintype "power_in"))
      (node (ref "LED26") (pin "1-VDD") (pinfunction "VDD_1-VDD") (pintype "power_in"))
      (node (ref "LED27") (pin "1-VDD") (pinfunction "VDD_1-VDD") (pintype "power_in"))
      (node (ref "LED28") (pin "1-VDD") (pinfunction "VDD_1-VDD") (pintype "power_in"))
      (node (ref "LED29") (pin "1-VDD") (pinfunction "VDD_1-VDD") (pintype "power_in"))
      (node (ref "LED3") (pin "1-VDD") (pinfunction "VDD_1-VDD") (pintype "power_in"))
      (node (ref "LED30") (pin "1-VDD") (pinfunction "VDD_1-VDD") (pintype "power_in"))
      (node (ref "LED31") (pin "1-VDD") (pinfunction "VDD_1-VDD") (pintype "power_in"))
      (node (ref "LED32") (pin "1-VDD") (pinfunction "VDD_1-VDD") (pintype "power_in"))
      (node (ref "LED33") (pin "1-VDD") (pinfunction "VDD_1-VDD") (pintype "power_in"))
      (node (ref "LED34") (pin "1-VDD") (pinfunction "VDD_1-VDD") (pintype "power_in"))
      (node (ref "LED35") (pin "1-VDD") (pinfunction "VDD_1-VDD") (pintype "power_in"))
      (node (ref "LED36") (pin "1-VDD") (pinfunction "VDD_1-VDD") (pintype "power_in"))
      (node (ref "LED37") (pin "1-VDD") (pinfunction "VDD_1-VDD") (pintype "power_in"))
      (node (ref "LED4") (pin "1-VDD") (pinfunction "VDD_1-VDD") (pintype "power_in"))
      (node (ref "LED5") (pin "1-VDD") (pinfunction "VDD_1-VDD") (pintype "power_in"))
      (node (ref "LED6") (pin "1-VDD") (pinfunction "VDD_1-VDD") (pintype "power_in"))
      (node (ref "LED7") (pin "1-VDD") (pinfunction "VDD_1-VDD") (pintype "power_in"))
      (node (ref "LED8") (pin "1-VDD") (pinfunction "VDD_1-VDD") (pintype "power_in"))
      (node (ref "LED9") (pin "1-VDD") (pinfunction "VDD_1-VDD") (pintype "power_in"))
    )
  )
)
